# Canbus-Proto.net
KiCad netlist of a schematic drawn in EAGLE
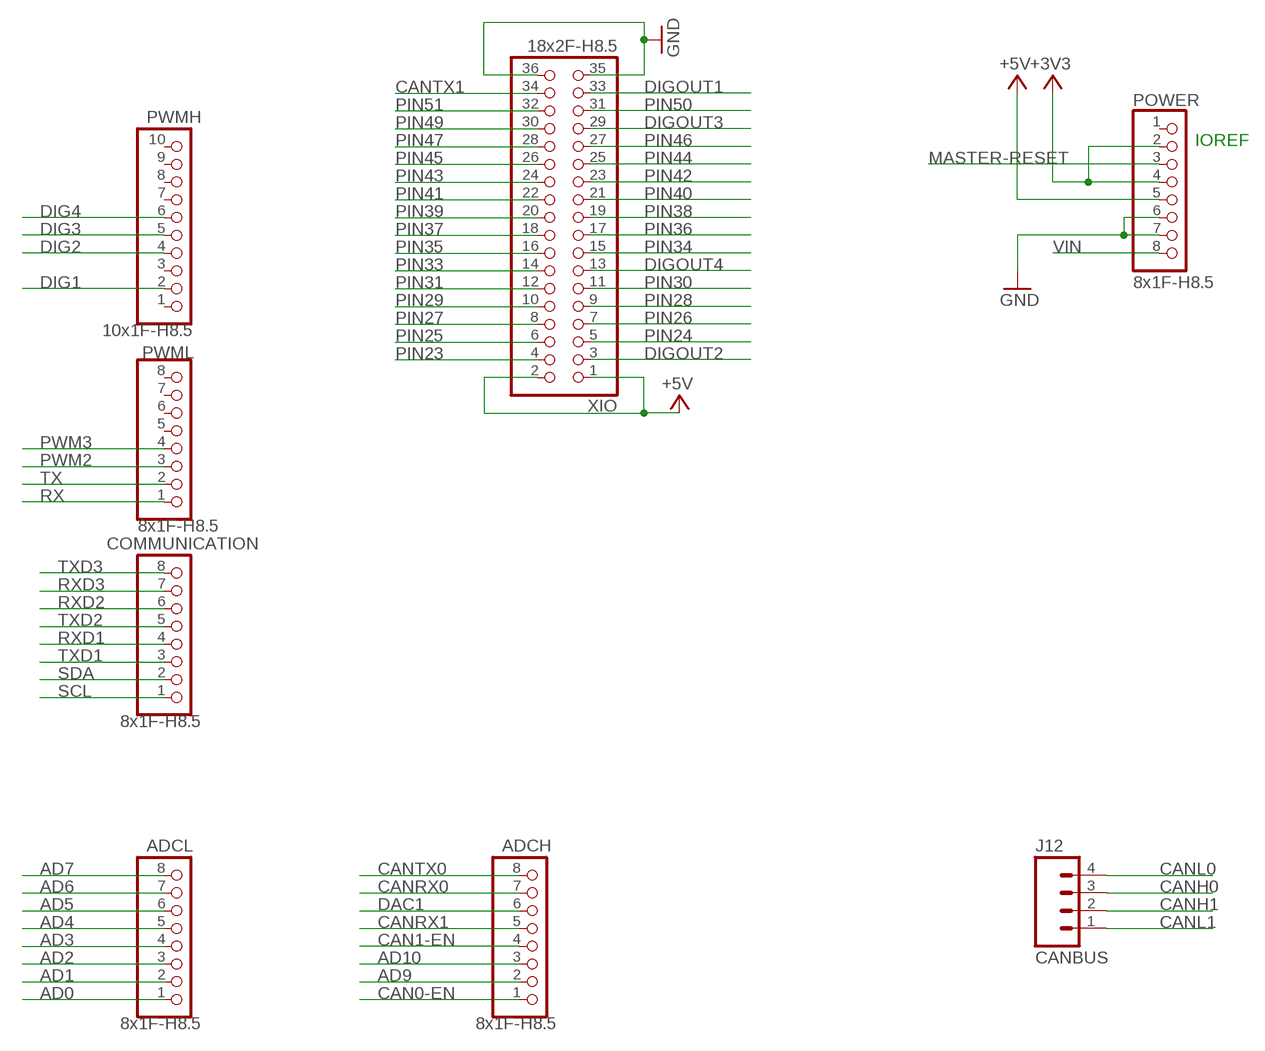
[diagram p0: schematic, sheet 1, part 1 of 2]
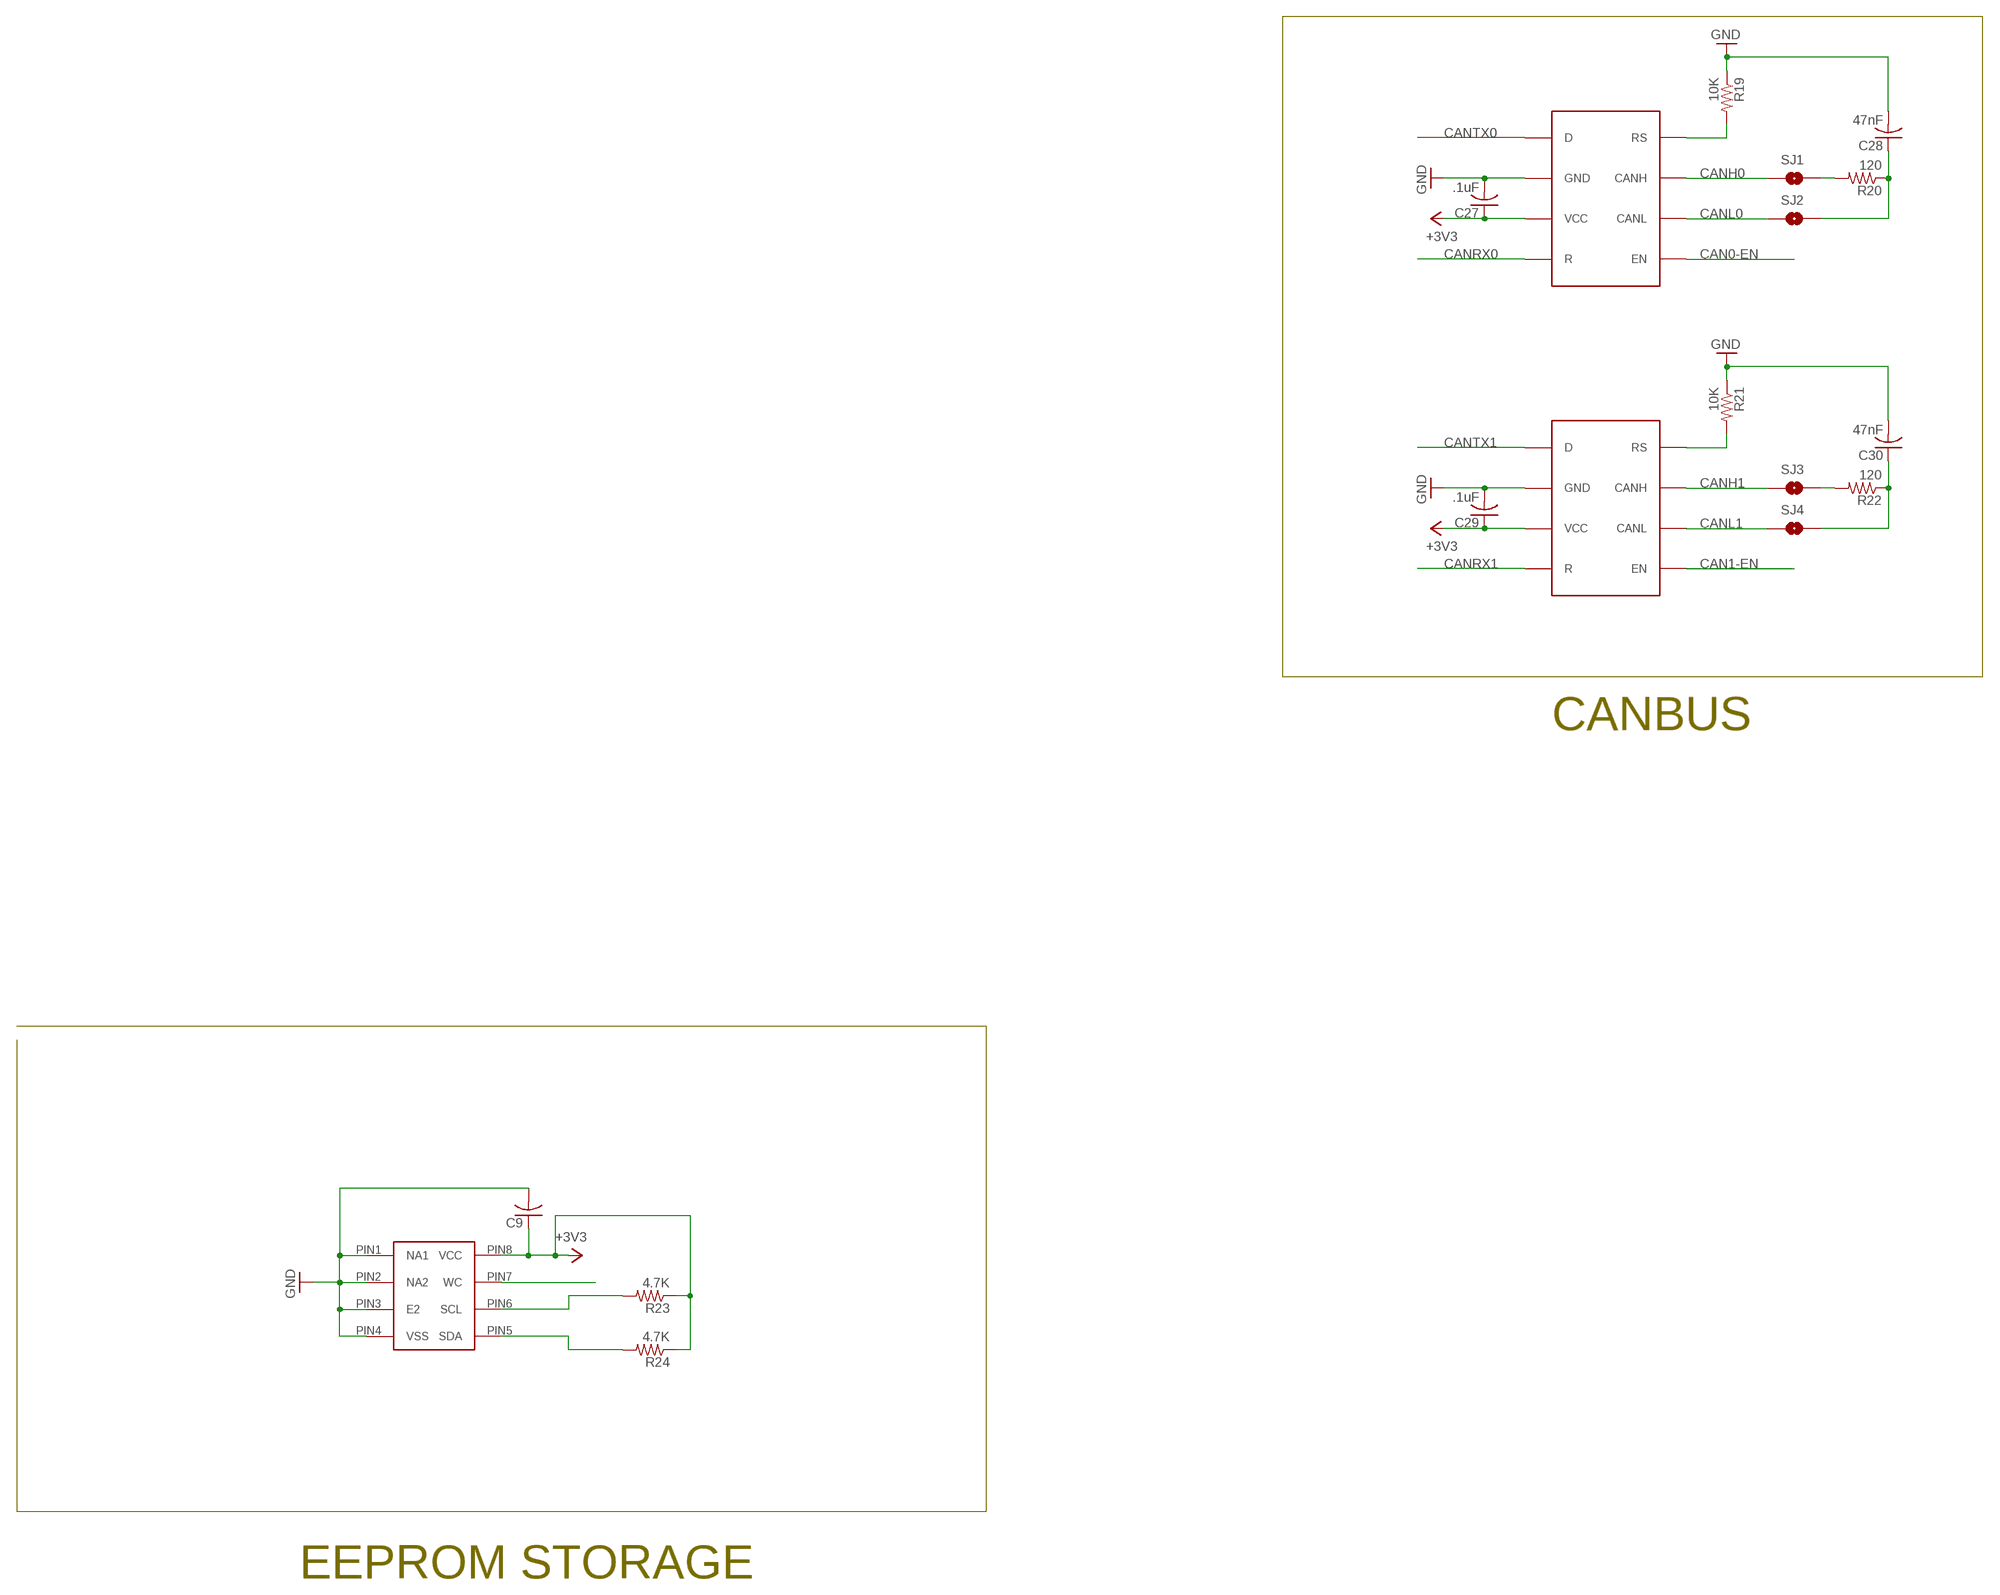
[diagram p1: schematic, sheet 1, part 2 of 2]

(export (version "E")
  (design (tool "Eeschema 10.0.6"))
  (components
    (comp (ref "ADCH")
      (value "8x1F-H8.5")
      (footprint "eagle-import:1X08")
      (libsource (lib "eagle-import") (part "PINHD-1X8"))
    )
    (comp (ref "ADCL")
      (value "8x1F-H8.5")
      (footprint "eagle-import:1X08")
      (libsource (lib "eagle-import") (part "PINHD-1X8"))
    )
    (comp (ref "C9")
      (value "C-USC0603")
      (footprint "eagle-import:C0603")
      (libsource (lib "eagle-import") (part "C-USC0603"))
    )
    (comp (ref "C27")
      (value ".1uF")
      (footprint "eagle-import:C0603")
      (libsource (lib "eagle-import") (part "C-USC0603"))
    )
    (comp (ref "C28")
      (value "47nF")
      (footprint "eagle-import:C0603")
      (libsource (lib "eagle-import") (part "C-USC0603"))
    )
    (comp (ref "C29")
      (value ".1uF")
      (footprint "eagle-import:C0603")
      (libsource (lib "eagle-import") (part "C-USC0603"))
    )
    (comp (ref "C30")
      (value "47nF")
      (footprint "eagle-import:C0603")
      (libsource (lib "eagle-import") (part "C-USC0603"))
    )
    (comp (ref "COMMUNICATION")
      (value "8x1F-H8.5")
      (footprint "eagle-import:1X08")
      (libsource (lib "eagle-import") (part "PINHD-1X8"))
    )
    (comp (ref "J12")
      (value "CANBUS")
      (footprint "eagle-import:1X04")
      (libsource (lib "eagle-import") (part "M04PTH"))
    )
    (comp (ref "POWER")
      (value "8x1F-H8.5")
      (footprint "eagle-import:1X08")
      (libsource (lib "eagle-import") (part "PINHD-1X8"))
    )
    (comp (ref "PWMH")
      (value "10x1F-H8.5")
      (footprint "eagle-import:1X10")
      (libsource (lib "eagle-import") (part "PINHD-1X10"))
    )
    (comp (ref "PWML")
      (value "8x1F-H8.5")
      (footprint "eagle-import:1X08")
      (libsource (lib "eagle-import") (part "PINHD-1X8"))
    )
    (comp (ref "R19")
      (value "10K")
      (footprint "eagle-import:R0603")
      (libsource (lib "eagle-import") (part "R-US_R0603"))
    )
    (comp (ref "R20")
      (value "120")
      (footprint "eagle-import:R0603")
      (libsource (lib "eagle-import") (part "R-US_R0603"))
    )
    (comp (ref "R21")
      (value "10K")
      (footprint "eagle-import:R0603")
      (libsource (lib "eagle-import") (part "R-US_R0603"))
    )
    (comp (ref "R22")
      (value "120")
      (footprint "eagle-import:R0603")
      (libsource (lib "eagle-import") (part "R-US_R0603"))
    )
    (comp (ref "R23")
      (value "4.7K")
      (footprint "eagle-import:R0603")
      (libsource (lib "eagle-import") (part "R-US_R0603"))
    )
    (comp (ref "R24")
      (value "4.7K")
      (footprint "eagle-import:R0603")
      (libsource (lib "eagle-import") (part "R-US_R0603"))
    )
    (comp (ref "SJ1")
      (value "SOLDERJUMPERNO")
      (footprint "eagle-import:SJ_2S-NO")
      (libsource (lib "eagle-import") (part "SOLDERJUMPERNO"))
    )
    (comp (ref "SJ2")
      (value "SOLDERJUMPERNO")
      (footprint "eagle-import:SJ_2S-NO")
      (libsource (lib "eagle-import") (part "SOLDERJUMPERNO"))
    )
    (comp (ref "SJ3")
      (value "SOLDERJUMPERNO")
      (footprint "eagle-import:SJ_2S-NO")
      (libsource (lib "eagle-import") (part "SOLDERJUMPERNO"))
    )
    (comp (ref "SJ4")
      (value "SOLDERJUMPERNO")
      (footprint "eagle-import:SJ_2S-NO")
      (libsource (lib "eagle-import") (part "SOLDERJUMPERNO"))
    )
    (comp (ref "U$2")
      (value "SN65HVD234")
      (footprint "eagle-import:SOIC8")
      (libsource (lib "eagle-import") (part "SN65HVD234"))
    )
    (comp (ref "U$5")
      (value "M24M02-DRMN6TP")
      (footprint "eagle-import:SOIC8")
      (libsource (lib "eagle-import") (part "M24M02-DRMN6TP"))
    )
    (comp (ref "U$6")
      (value "SN65HVD234")
      (footprint "eagle-import:SOIC8")
      (libsource (lib "eagle-import") (part "SN65HVD234"))
    )
    (comp (ref "XIO")
      (value "18x2F-H8.5")
      (footprint "eagle-import:2X18")
      (libsource (lib "eagle-import") (part "PINHD-2X18"))
    )
  )
  (nets
    (net (code "1") (name "+3V3") (class "Default")
      (node (ref "C27") (pin "1") (pinfunction "1_1") (pintype "passive"))
      (node (ref "C29") (pin "1") (pinfunction "1_1") (pintype "passive"))
      (node (ref "C9") (pin "1") (pinfunction "1_1") (pintype "passive"))
      (node (ref "POWER") (pin "2") (pinfunction "2_2") (pintype "passive"))
      (node (ref "POWER") (pin "4") (pinfunction "4_4") (pintype "passive"))
      (node (ref "R23") (pin "1") (pinfunction "1_1") (pintype "passive"))
      (node (ref "R24") (pin "1") (pinfunction "1_1") (pintype "passive"))
      (node (ref "U$2") (pin "PIN3") (pinfunction "VCC_PIN3") (pintype "bidirectional"))
      (node (ref "U$5") (pin "PIN8") (pinfunction "VCC_PIN8") (pintype "bidirectional"))
      (node (ref "U$6") (pin "PIN3") (pinfunction "VCC_PIN3") (pintype "bidirectional"))
    )
    (net (code "2") (name "+5V") (class "Default")
      (node (ref "POWER") (pin "5") (pinfunction "5_5") (pintype "passive"))
      (node (ref "XIO") (pin "1") (pinfunction "1_1") (pintype "passive"))
      (node (ref "XIO") (pin "2") (pinfunction "2_2") (pintype "passive"))
    )
    (net (code "3") (name "/AD0") (class "Default")
      (node (ref "ADCL") (pin "1") (pinfunction "1_1") (pintype "passive"))
    )
    (net (code "4") (name "/AD1") (class "Default")
      (node (ref "ADCL") (pin "2") (pinfunction "2_2") (pintype "passive"))
    )
    (net (code "5") (name "/AD2") (class "Default")
      (node (ref "ADCL") (pin "3") (pinfunction "3_3") (pintype "passive"))
    )
    (net (code "6") (name "/AD3") (class "Default")
      (node (ref "ADCL") (pin "4") (pinfunction "4_4") (pintype "passive"))
    )
    (net (code "7") (name "/AD4") (class "Default")
      (node (ref "ADCL") (pin "5") (pinfunction "5_5") (pintype "passive"))
    )
    (net (code "8") (name "/AD5") (class "Default")
      (node (ref "ADCL") (pin "6") (pinfunction "6_6") (pintype "passive"))
    )
    (net (code "9") (name "/AD6") (class "Default")
      (node (ref "ADCL") (pin "7") (pinfunction "7_7") (pintype "passive"))
    )
    (net (code "10") (name "/AD7") (class "Default")
      (node (ref "ADCL") (pin "8") (pinfunction "8_8") (pintype "passive"))
    )
    (net (code "11") (name "/AD9") (class "Default")
      (node (ref "ADCH") (pin "2") (pinfunction "2_2") (pintype "passive"))
    )
    (net (code "12") (name "/AD10") (class "Default")
      (node (ref "ADCH") (pin "3") (pinfunction "3_3") (pintype "passive"))
    )
    (net (code "13") (name "/CAN0-EN") (class "Default")
      (node (ref "ADCH") (pin "1") (pinfunction "1_1") (pintype "passive"))
      (node (ref "U$6") (pin "PIN5") (pinfunction "EN_PIN5") (pintype "bidirectional"))
    )
    (net (code "14") (name "/CAN1-EN") (class "Default")
      (node (ref "ADCH") (pin "4") (pinfunction "4_4") (pintype "passive"))
      (node (ref "U$2") (pin "PIN5") (pinfunction "EN_PIN5") (pintype "bidirectional"))
    )
    (net (code "15") (name "/CANH0") (class "Default")
      (node (ref "J12") (pin "3") (pinfunction "3_3") (pintype "passive"))
      (node (ref "SJ1") (pin "1") (pinfunction "1_1") (pintype "passive"))
      (node (ref "U$6") (pin "PIN7") (pinfunction "CANH_PIN7") (pintype "bidirectional"))
    )
    (net (code "16") (name "/CANH1") (class "Default")
      (node (ref "J12") (pin "2") (pinfunction "2_2") (pintype "passive"))
      (node (ref "SJ3") (pin "1") (pinfunction "1_1") (pintype "passive"))
      (node (ref "U$2") (pin "PIN7") (pinfunction "CANH_PIN7") (pintype "bidirectional"))
    )
    (net (code "17") (name "/CANL0") (class "Default")
      (node (ref "J12") (pin "4") (pinfunction "4_4") (pintype "passive"))
      (node (ref "SJ2") (pin "1") (pinfunction "1_1") (pintype "passive"))
      (node (ref "U$6") (pin "PIN6") (pinfunction "CANL_PIN6") (pintype "bidirectional"))
    )
    (net (code "18") (name "/CANL1") (class "Default")
      (node (ref "J12") (pin "1") (pinfunction "1_1") (pintype "passive"))
      (node (ref "SJ4") (pin "1") (pinfunction "1_1") (pintype "passive"))
      (node (ref "U$2") (pin "PIN6") (pinfunction "CANL_PIN6") (pintype "bidirectional"))
    )
    (net (code "19") (name "/CANRX0") (class "Default")
      (node (ref "ADCH") (pin "7") (pinfunction "7_7") (pintype "passive"))
      (node (ref "U$6") (pin "PIN4") (pinfunction "R_PIN4") (pintype "bidirectional"))
    )
    (net (code "20") (name "/CANRX1") (class "Default")
      (node (ref "ADCH") (pin "5") (pinfunction "5_5") (pintype "passive"))
      (node (ref "U$2") (pin "PIN4") (pinfunction "R_PIN4") (pintype "bidirectional"))
    )
    (net (code "21") (name "/CANTX0") (class "Default")
      (node (ref "ADCH") (pin "8") (pinfunction "8_8") (pintype "passive"))
      (node (ref "U$6") (pin "PIN1") (pinfunction "D_PIN1") (pintype "bidirectional"))
    )
    (net (code "22") (name "/CANTX1") (class "Default")
      (node (ref "U$2") (pin "PIN1") (pinfunction "D_PIN1") (pintype "bidirectional"))
      (node (ref "XIO") (pin "34") (pinfunction "34_34") (pintype "passive"))
    )
    (net (code "23") (name "/DAC1") (class "Default")
      (node (ref "ADCH") (pin "6") (pinfunction "6_6") (pintype "passive"))
    )
    (net (code "24") (name "/DIG1") (class "Default")
      (node (ref "PWMH") (pin "2") (pinfunction "2_2") (pintype "passive"))
    )
    (net (code "25") (name "/DIG2") (class "Default")
      (node (ref "PWMH") (pin "4") (pinfunction "4_4") (pintype "passive"))
    )
    (net (code "26") (name "/DIG3") (class "Default")
      (node (ref "PWMH") (pin "5") (pinfunction "5_5") (pintype "passive"))
    )
    (net (code "27") (name "/DIG4") (class "Default")
      (node (ref "PWMH") (pin "6") (pinfunction "6_6") (pintype "passive"))
    )
    (net (code "28") (name "/DIGOUT1") (class "Default")
      (node (ref "XIO") (pin "33") (pinfunction "33_33") (pintype "passive"))
    )
    (net (code "29") (name "/DIGOUT2") (class "Default")
      (node (ref "XIO") (pin "3") (pinfunction "3_3") (pintype "passive"))
    )
    (net (code "30") (name "/DIGOUT3") (class "Default")
      (node (ref "XIO") (pin "29") (pinfunction "29_29") (pintype "passive"))
    )
    (net (code "31") (name "/DIGOUT4") (class "Default")
      (node (ref "XIO") (pin "13") (pinfunction "13_13") (pintype "passive"))
    )
    (net (code "32") (name "/MASTER-RESET") (class "Default")
      (node (ref "POWER") (pin "3") (pinfunction "3_3") (pintype "passive"))
    )
    (net (code "33") (name "/PIN23") (class "Default")
      (node (ref "XIO") (pin "4") (pinfunction "4_4") (pintype "passive"))
    )
    (net (code "34") (name "/PIN24") (class "Default")
      (node (ref "XIO") (pin "5") (pinfunction "5_5") (pintype "passive"))
    )
    (net (code "35") (name "/PIN25") (class "Default")
      (node (ref "XIO") (pin "6") (pinfunction "6_6") (pintype "passive"))
    )
    (net (code "36") (name "/PIN26") (class "Default")
      (node (ref "XIO") (pin "7") (pinfunction "7_7") (pintype "passive"))
    )
    (net (code "37") (name "/PIN27") (class "Default")
      (node (ref "XIO") (pin "8") (pinfunction "8_8") (pintype "passive"))
    )
    (net (code "38") (name "/PIN28") (class "Default")
      (node (ref "XIO") (pin "9") (pinfunction "9_9") (pintype "passive"))
    )
    (net (code "39") (name "/PIN29") (class "Default")
      (node (ref "XIO") (pin "10") (pinfunction "10_10") (pintype "passive"))
    )
    (net (code "40") (name "/PIN30") (class "Default")
      (node (ref "XIO") (pin "11") (pinfunction "11_11") (pintype "passive"))
    )
    (net (code "41") (name "/PIN31") (class "Default")
      (node (ref "XIO") (pin "12") (pinfunction "12_12") (pintype "passive"))
    )
    (net (code "42") (name "/PIN33") (class "Default")
      (node (ref "XIO") (pin "14") (pinfunction "14_14") (pintype "passive"))
    )
    (net (code "43") (name "/PIN34") (class "Default")
      (node (ref "XIO") (pin "15") (pinfunction "15_15") (pintype "passive"))
    )
    (net (code "44") (name "/PIN35") (class "Default")
      (node (ref "XIO") (pin "16") (pinfunction "16_16") (pintype "passive"))
    )
    (net (code "45") (name "/PIN36") (class "Default")
      (node (ref "XIO") (pin "17") (pinfunction "17_17") (pintype "passive"))
    )
    (net (code "46") (name "/PIN37") (class "Default")
      (node (ref "XIO") (pin "18") (pinfunction "18_18") (pintype "passive"))
    )
    (net (code "47") (name "/PIN38") (class "Default")
      (node (ref "XIO") (pin "19") (pinfunction "19_19") (pintype "passive"))
    )
    (net (code "48") (name "/PIN39") (class "Default")
      (node (ref "XIO") (pin "20") (pinfunction "20_20") (pintype "passive"))
    )
    (net (code "49") (name "/PIN40") (class "Default")
      (node (ref "XIO") (pin "21") (pinfunction "21_21") (pintype "passive"))
    )
    (net (code "50") (name "/PIN41") (class "Default")
      (node (ref "XIO") (pin "22") (pinfunction "22_22") (pintype "passive"))
    )
    (net (code "51") (name "/PIN42") (class "Default")
      (node (ref "XIO") (pin "23") (pinfunction "23_23") (pintype "passive"))
    )
    (net (code "52") (name "/PIN43") (class "Default")
      (node (ref "XIO") (pin "24") (pinfunction "24_24") (pintype "passive"))
    )
    (net (code "53") (name "/PIN44") (class "Default")
      (node (ref "XIO") (pin "25") (pinfunction "25_25") (pintype "passive"))
    )
    (net (code "54") (name "/PIN45") (class "Default")
      (node (ref "XIO") (pin "26") (pinfunction "26_26") (pintype "passive"))
    )
    (net (code "55") (name "/PIN46") (class "Default")
      (node (ref "XIO") (pin "27") (pinfunction "27_27") (pintype "passive"))
    )
    (net (code "56") (name "/PIN47") (class "Default")
      (node (ref "XIO") (pin "28") (pinfunction "28_28") (pintype "passive"))
    )
    (net (code "57") (name "/PIN49") (class "Default")
      (node (ref "XIO") (pin "30") (pinfunction "30_30") (pintype "passive"))
    )
    (net (code "58") (name "/PIN50") (class "Default")
      (node (ref "XIO") (pin "31") (pinfunction "31_31") (pintype "passive"))
    )
    (net (code "59") (name "/PIN51") (class "Default")
      (node (ref "XIO") (pin "32") (pinfunction "32_32") (pintype "passive"))
    )
    (net (code "60") (name "/PWM2") (class "Default")
      (node (ref "PWML") (pin "3") (pinfunction "3_3") (pintype "passive"))
    )
    (net (code "61") (name "/PWM3") (class "Default")
      (node (ref "PWML") (pin "4") (pinfunction "4_4") (pintype "passive"))
    )
    (net (code "62") (name "/RX") (class "Default")
      (node (ref "PWML") (pin "1") (pinfunction "1_1") (pintype "passive"))
    )
    (net (code "63") (name "/RXD1") (class "Default")
      (node (ref "COMMUNICATION") (pin "4") (pinfunction "4_4") (pintype "passive"))
      (node (ref "U$5") (pin "PIN7") (pinfunction "WC_PIN7") (pintype "bidirectional"))
    )
    (net (code "64") (name "/RXD2") (class "Default")
      (node (ref "COMMUNICATION") (pin "6") (pinfunction "6_6") (pintype "passive"))
    )
    (net (code "65") (name "/RXD3") (class "Default")
      (node (ref "COMMUNICATION") (pin "7") (pinfunction "7_7") (pintype "passive"))
    )
    (net (code "66") (name "/SCL") (class "Default")
      (node (ref "COMMUNICATION") (pin "1") (pinfunction "1_1") (pintype "passive"))
      (node (ref "R23") (pin "2") (pinfunction "2_2") (pintype "passive"))
      (node (ref "U$5") (pin "PIN6") (pinfunction "SCL_PIN6") (pintype "bidirectional"))
    )
    (net (code "67") (name "/SDA") (class "Default")
      (node (ref "COMMUNICATION") (pin "2") (pinfunction "2_2") (pintype "passive"))
      (node (ref "R24") (pin "2") (pinfunction "2_2") (pintype "passive"))
      (node (ref "U$5") (pin "PIN5") (pinfunction "SDA_PIN5") (pintype "bidirectional"))
    )
    (net (code "68") (name "/TX") (class "Default")
      (node (ref "PWML") (pin "2") (pinfunction "2_2") (pintype "passive"))
    )
    (net (code "69") (name "/TXD1") (class "Default")
      (node (ref "COMMUNICATION") (pin "3") (pinfunction "3_3") (pintype "passive"))
    )
    (net (code "70") (name "/TXD2") (class "Default")
      (node (ref "COMMUNICATION") (pin "5") (pinfunction "5_5") (pintype "passive"))
    )
    (net (code "71") (name "/TXD3") (class "Default")
      (node (ref "COMMUNICATION") (pin "8") (pinfunction "8_8") (pintype "passive"))
    )
    (net (code "72") (name "/VIN") (class "Default")
      (node (ref "POWER") (pin "8") (pinfunction "8_8") (pintype "passive"))
    )
    (net (code "73") (name "GND") (class "Default")
      (node (ref "C27") (pin "2") (pinfunction "2_2") (pintype "passive"))
      (node (ref "C28") (pin "2") (pinfunction "2_2") (pintype "passive"))
      (node (ref "C29") (pin "2") (pinfunction "2_2") (pintype "passive"))
      (node (ref "C30") (pin "2") (pinfunction "2_2") (pintype "passive"))
      (node (ref "C9") (pin "2") (pinfunction "2_2") (pintype "passive"))
      (node (ref "POWER") (pin "6") (pinfunction "6_6") (pintype "passive"))
      (node (ref "POWER") (pin "7") (pinfunction "7_7") (pintype "passive"))
      (node (ref "R19") (pin "1") (pinfunction "1_1") (pintype "passive"))
      (node (ref "R21") (pin "1") (pinfunction "1_1") (pintype "passive"))
      (node (ref "U$2") (pin "PIN2") (pinfunction "GND_PIN2") (pintype "bidirectional"))
      (node (ref "U$5") (pin "PIN1") (pinfunction "NA1_PIN1") (pintype "bidirectional"))
      (node (ref "U$5") (pin "PIN2") (pinfunction "NA2_PIN2") (pintype "bidirectional"))
      (node (ref "U$5") (pin "PIN3") (pinfunction "E2_PIN3") (pintype "bidirectional"))
      (node (ref "U$5") (pin "PIN4") (pinfunction "VSS_PIN4") (pintype "bidirectional"))
      (node (ref "U$6") (pin "PIN2") (pinfunction "GND_PIN2") (pintype "bidirectional"))
      (node (ref "XIO") (pin "35") (pinfunction "35_35") (pintype "passive"))
      (node (ref "XIO") (pin "36") (pinfunction "36_36") (pintype "passive"))
    )
    (net (code "74") (name "Net-(C28-Pad1)") (class "Default")
      (node (ref "C28") (pin "1") (pinfunction "1_1") (pintype "passive"))
      (node (ref "R20") (pin "1") (pinfunction "1_1") (pintype "passive"))
      (node (ref "SJ2") (pin "2") (pinfunction "2_2") (pintype "passive"))
    )
    (net (code "75") (name "Net-(C30-Pad1)") (class "Default")
      (node (ref "C30") (pin "1") (pinfunction "1_1") (pintype "passive"))
      (node (ref "R22") (pin "1") (pinfunction "1_1") (pintype "passive"))
      (node (ref "SJ4") (pin "2") (pinfunction "2_2") (pintype "passive"))
    )
    (net (code "76") (name "Net-(R20-Pad2)") (class "Default")
      (node (ref "R20") (pin "2") (pinfunction "2_2") (pintype "passive"))
      (node (ref "SJ1") (pin "2") (pinfunction "2_2") (pintype "passive"))
    )
    (net (code "77") (name "Net-(R22-Pad2)") (class "Default")
      (node (ref "R22") (pin "2") (pinfunction "2_2") (pintype "passive"))
      (node (ref "SJ3") (pin "2") (pinfunction "2_2") (pintype "passive"))
    )
    (net (code "78") (name "Net-(U$2-RS)") (class "Default")
      (node (ref "R21") (pin "2") (pinfunction "2_2") (pintype "passive"))
      (node (ref "U$2") (pin "PIN8") (pinfunction "RS_PIN8") (pintype "bidirectional"))
    )
    (net (code "79") (name "Net-(U$6-RS)") (class "Default")
      (node (ref "R19") (pin "2") (pinfunction "2_2") (pintype "passive"))
      (node (ref "U$6") (pin "PIN8") (pinfunction "RS_PIN8") (pintype "bidirectional"))
    )
    (net (code "80") (name "unconnected-(POWER-Pad1)") (class "Default")
      (node (ref "POWER") (pin "1") (pinfunction "1_1") (pintype "passive"))
    )
    (net (code "81") (name "unconnected-(PWMH-Pad1)") (class "Default")
      (node (ref "PWMH") (pin "1") (pinfunction "1_1") (pintype "passive"))
    )
    (net (code "82") (name "unconnected-(PWMH-Pad3)") (class "Default")
      (node (ref "PWMH") (pin "3") (pinfunction "3_3") (pintype "passive"))
    )
    (net (code "83") (name "unconnected-(PWMH-Pad7)") (class "Default")
      (node (ref "PWMH") (pin "7") (pinfunction "7_7") (pintype "passive"))
    )
    (net (code "84") (name "unconnected-(PWMH-Pad8)") (class "Default")
      (node (ref "PWMH") (pin "8") (pinfunction "8_8") (pintype "passive"))
    )
    (net (code "85") (name "unconnected-(PWMH-Pad9)") (class "Default")
      (node (ref "PWMH") (pin "9") (pinfunction "9_9") (pintype "passive"))
    )
    (net (code "86") (name "unconnected-(PWMH-Pad10)") (class "Default")
      (node (ref "PWMH") (pin "10") (pinfunction "10_10") (pintype "passive"))
    )
    (net (code "87") (name "unconnected-(PWML-Pad5)") (class "Default")
      (node (ref "PWML") (pin "5") (pinfunction "5_5") (pintype "passive"))
    )
    (net (code "88") (name "unconnected-(PWML-Pad6)") (class "Default")
      (node (ref "PWML") (pin "6") (pinfunction "6_6") (pintype "passive"))
    )
    (net (code "89") (name "unconnected-(PWML-Pad7)") (class "Default")
      (node (ref "PWML") (pin "7") (pinfunction "7_7") (pintype "passive"))
    )
    (net (code "90") (name "unconnected-(PWML-Pad8)") (class "Default")
      (node (ref "PWML") (pin "8") (pinfunction "8_8") (pintype "passive"))
    )
  )
)
